# Disch_Sch.net
KiCad netlist of a schematic drawn in Altium Designer
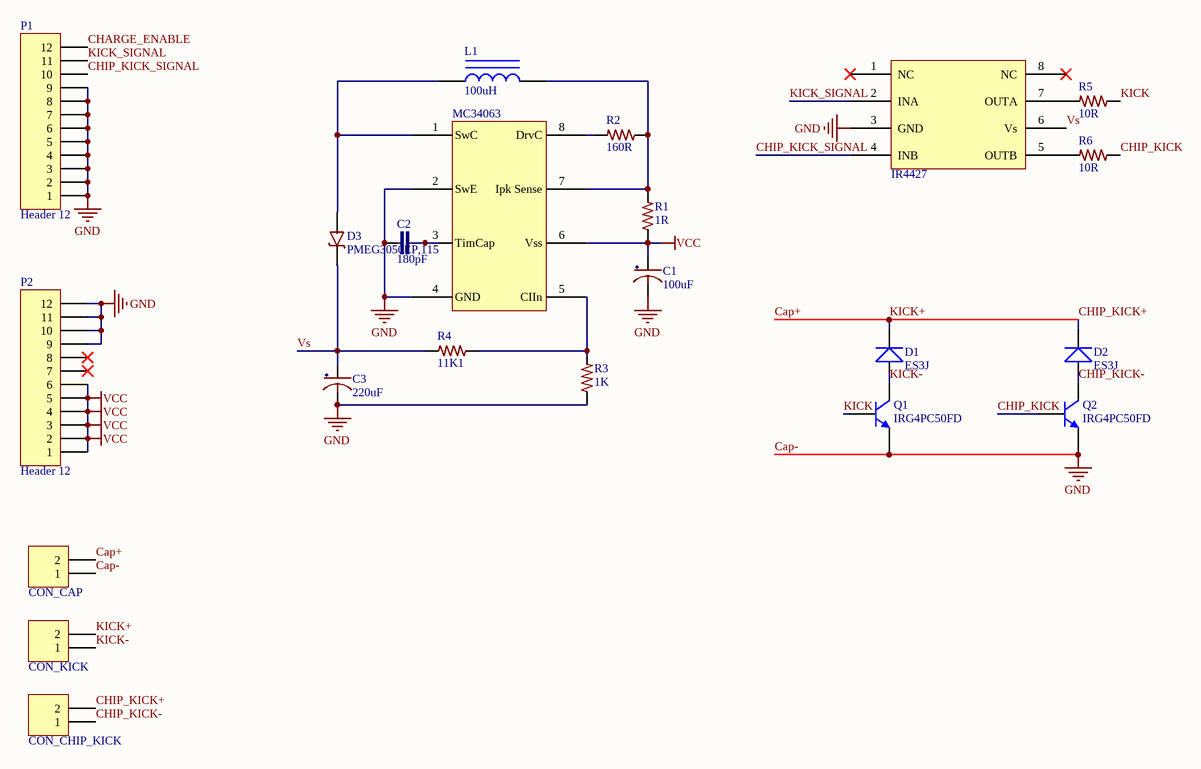
[diagram p0: Disch_Sch.SchDoc]

(export (version "E")
  (design (tool "Eeschema 10.0.6"))
  (components
    (comp (ref "C1")
      (value "100uF")
      (footprint "7343-CAPPOL")
      (description "CAP TANT 100uF 25V 20% ESR = 30mOhm @ 100 kHz")
      (fields (field (name "PART NO") "T521X107M025ATE030"))
      (libsource (lib "IMBEL") (part "CT2917-100uF-1"))
    )
    (comp (ref "C2")
      (value "180pF")
      (footprint "0805-CAP")
      (description "CAP CER 180PF 50V NP0 0805")
      (fields (field (name "PART NO") "C0805C181K5GACTU"))
      (libsource (lib "IMBEL") (part "CC0805-180pF-2"))
    )
    (comp (ref "C3")
      (value "220uF")
      (footprint "NIC-CAPA2-10X10_V")
      (description "CAP ALUM 220uF 20% 50V  ESR = 0,18 ohms  Radial DIA 10mm HEIGH 10,2mm")
      (fields (field (name "PART NO") "EEEFK1H221P"))
      (libsource (lib "IMBEL") (part "CAPACITOR-POL"))
    )
    (comp (ref "CON_CAP")
      (value "OSTTA024163")
      (footprint "Term Block 2P")
      (description "2 Position Wire to Board Terminal Block Horizontal with Board 0.200\" (5.08mm) Through Hole")
      (libsource (lib "Schlib1") (part "Term Block 2P"))
    )
    (comp (ref "CON_CHIP_KICK")
      (value "OSTTA024163")
      (footprint "Term Block 2P")
      (description "2 Position Wire to Board Terminal Block Horizontal with Board 0.200\" (5.08mm) Through Hole")
      (libsource (lib "Schlib1") (part "Term Block 2P"))
    )
    (comp (ref "CON_KICK")
      (value "OSTTA024163")
      (footprint "Term Block 2P")
      (description "2 Position Wire to Board Terminal Block Horizontal with Board 0.200\" (5.08mm) Through Hole")
      (libsource (lib "Schlib1") (part "Term Block 2P"))
    )
    (comp (ref "D1") (value "ES3J") (footprint "Diode") (libsource (lib "KickerSchlib") (part "ES3J")))
    (comp (ref "D2") (value "ES3J") (footprint "Diode") (libsource (lib "KickerSchlib") (part "ES3J")))
    (comp (ref "D3")
      (value "PMEG3050EP,115")
      (footprint "PCBComponent")
      (description "DIODE SCHOTTKY 30V 5A SOD128")
      (libsource (lib "IMBEL") (part "PMEG3050EP,115-01.A.5"))
    )
    (comp (ref "IR4427")
      (value "GATE DRIVER")
      (footprint "IR4427")
      (description "IC DRIVER DUAL LOW SIDE 8-SOIC")
      (libsource (lib "KickerSchlib") (part "IR4427"))
    )
    (comp (ref "L1")
      (value "100uH")
      (footprint "INDUCTOR")
      (description "Fixed Inductors 100uH 0.86A SMT")
      (libsource (lib "KickerSchlib") (part "Inductor"))
    )
    (comp (ref "MC34063")
      (value "Switching Voltage Regulator")
      (footprint "MC34063")
      (libsource (lib "Schlib1") (part "MC34063"))
    )
    (comp (ref "P1")
      (value "Header 12")
      (footprint "HDR1X12")
      (description "Header, 12-Pin")
      (fields (field (name "PUBLISHER") "Altium Limited"))
      (libsource (lib "Miscellaneous Connectors") (part "Header 12"))
    )
    (comp (ref "P2")
      (value "Header 12")
      (footprint "HDR1X12")
      (description "Header, 12-Pin")
      (fields (field (name "PUBLISHER") "Altium Limited"))
      (libsource (lib "Miscellaneous Connectors") (part "Header 12"))
    )
    (comp (ref "Q1")
      (value "IRG4PC50FD")
      (footprint "IRG4PC50FD")
      (description "IGBT Transistors 600V FAST 1-8 KHZ COPACK IGBT")
      (fields (field (name "PUBLISHER") "RoboIME"))
      (libsource (lib "KickerSchlib") (part "IRG4PC50FD"))
    )
    (comp (ref "Q2")
      (value "IRG4PC50FD")
      (footprint "IRG4PC50FD")
      (description "IGBT Transistors 600V FAST 1-8 KHZ COPACK IGBT")
      (fields (field (name "PUBLISHER") "RoboIME"))
      (libsource (lib "KickerSchlib") (part "IRG4PC50FD"))
    )
    (comp (ref "R1")
      (value "1R")
      (footprint "0805-RES")
      (description "RES SMD 1 OHM 1% 1/8W 0805")
      (fields (field (name "PART NO") "CRCW08051R00FKEA"))
      (libsource (lib "IMBEL") (part "R0805-1R-1%-1"))
    )
    (comp (ref "R2")
      (value "160R")
      (footprint "0805-RES")
      (description "RES 160 OHM 1/8W .5% 0805 SMD")
      (fields (field (name "PART NO") "ERA-6AED161V"))
      (libsource (lib "IMBEL") (part "R0805-160R-5"))
    )
    (comp (ref "R3")
      (value "1K")
      (footprint "0402-RES-HD")
      (description "RES 1K OHM 1/10W 1% 0402 SMD")
      (fields (field (name "PART NO") "ERJ-2RKF1001X"))
      (libsource (lib "IMBEL") (part "R0402-1K-A.9"))
    )
    (comp (ref "R4")
      (value "11K1")
      (footprint "0402-RES-HD")
      (description "RES 11.1 KOHM 1/16W 0.1% 0402 SMD")
      (fields (field (name "PART NO") "TNPW040211K1BEED"))
      (libsource (lib "IMBEL") (part "R0402-11K1-1"))
    )
    (comp (ref "R5")
      (value "10R")
      (footprint "0402-RES-HD")
      (description "RES 10 OHM 1/10W 1% 0402 SMD")
      (fields (field (name "PART NO") "ERJ-2RKF10R0X"))
      (libsource (lib "IMBEL") (part "RESISTOR"))
    )
    (comp (ref "R6")
      (value "10R")
      (footprint "0402-RES-HD")
      (description "RES 10 OHM 1/10W 1% 0402 SMD")
      (fields (field (name "PART NO") "ERJ-2RKF10R0X"))
      (libsource (lib "IMBEL") (part "RESISTOR"))
    )
  )
  (nets
    (net (code "1") (name "/CHARGE_ENABLE") (class "Default")
      (node (ref "P1") (pin "12") (pinfunction "12_12") (pintype "passive"))
    )
    (net (code "2") (name "/CHIP_KICK") (class "Default")
      (node (ref "Q2") (pin "2") (pinfunction "G_2") (pintype "passive"))
      (node (ref "R6") (pin "2") (pinfunction "2_2") (pintype "passive"))
    )
    (net (code "3") (name "/CHIP_KICK+") (class "Default")
      (node (ref "CON_CAP") (pin "2") (pinfunction "2_2") (pintype "passive"))
      (node (ref "CON_CHIP_KICK") (pin "2") (pinfunction "2_2") (pintype "passive"))
      (node (ref "CON_KICK") (pin "2") (pinfunction "2_2") (pintype "passive"))
      (node (ref "D1") (pin "D1+") (pinfunction "D1+_D1+") (pintype "passive"))
      (node (ref "D2") (pin "D1+") (pinfunction "D1+_D1+") (pintype "passive"))
    )
    (net (code "4") (name "/CHIP_KICK-") (class "Default")
      (node (ref "CON_CHIP_KICK") (pin "1") (pinfunction "1_1") (pintype "passive"))
      (node (ref "D2") (pin "D1-") (pinfunction "D1-_D1-") (pintype "passive"))
      (node (ref "Q2") (pin "1") (pinfunction "C_1") (pintype "passive"))
    )
    (net (code "5") (name "/CHIP_KICK_SIGNAL") (class "Default")
      (node (ref "IR4427") (pin "4") (pinfunction "INB_4") (pintype "passive"))
      (node (ref "P1") (pin "10") (pinfunction "10_10") (pintype "passive"))
    )
    (net (code "6") (name "/KICK") (class "Default")
      (node (ref "Q1") (pin "2") (pinfunction "G_2") (pintype "passive"))
      (node (ref "R5") (pin "2") (pinfunction "2_2") (pintype "passive"))
    )
    (net (code "7") (name "/KICK-") (class "Default")
      (node (ref "CON_KICK") (pin "1") (pinfunction "1_1") (pintype "passive"))
      (node (ref "D1") (pin "D1-") (pinfunction "D1-_D1-") (pintype "passive"))
      (node (ref "Q1") (pin "1") (pinfunction "C_1") (pintype "passive"))
    )
    (net (code "8") (name "/KICK_SIGNAL") (class "Default")
      (node (ref "IR4427") (pin "2") (pinfunction "INA_2") (pintype "passive"))
      (node (ref "P1") (pin "11") (pinfunction "11_11") (pintype "passive"))
    )
    (net (code "9") (name "/Vs") (class "Default")
      (node (ref "C3") (pin "1") (pinfunction "+_1") (pintype "passive"))
      (node (ref "D3") (pin "1") (pinfunction "C_1") (pintype "passive"))
      (node (ref "IR4427") (pin "6") (pinfunction "Vs_6") (pintype "passive"))
      (node (ref "R4") (pin "1") (pinfunction "1_1") (pintype "passive"))
    )
    (net (code "10") (name "GND") (class "Default")
      (node (ref "C1") (pin "2") (pinfunction "-_2") (pintype "passive"))
      (node (ref "C2") (pin "1") (pinfunction "1_1") (pintype "passive"))
      (node (ref "C3") (pin "2") (pinfunction "-_2") (pintype "passive"))
      (node (ref "CON_CAP") (pin "1") (pinfunction "1_1") (pintype "passive"))
      (node (ref "IR4427") (pin "3") (pinfunction "GND_3") (pintype "passive"))
      (node (ref "MC34063") (pin "2") (pinfunction "SwE_2") (pintype "passive"))
      (node (ref "MC34063") (pin "4") (pinfunction "GND_4") (pintype "passive"))
      (node (ref "P1") (pin "1") (pinfunction "1_1") (pintype "passive"))
      (node (ref "P1") (pin "2") (pinfunction "2_2") (pintype "passive"))
      (node (ref "P1") (pin "3") (pinfunction "3_3") (pintype "passive"))
      (node (ref "P1") (pin "4") (pinfunction "4_4") (pintype "passive"))
      (node (ref "P1") (pin "5") (pinfunction "5_5") (pintype "passive"))
      (node (ref "P1") (pin "6") (pinfunction "6_6") (pintype "passive"))
      (node (ref "P1") (pin "7") (pinfunction "7_7") (pintype "passive"))
      (node (ref "P1") (pin "8") (pinfunction "8_8") (pintype "passive"))
      (node (ref "P1") (pin "9") (pinfunction "9_9") (pintype "passive"))
      (node (ref "P2") (pin "10") (pinfunction "10_10") (pintype "passive"))
      (node (ref "P2") (pin "11") (pinfunction "11_11") (pintype "passive"))
      (node (ref "P2") (pin "12") (pinfunction "12_12") (pintype "passive"))
      (node (ref "P2") (pin "9") (pinfunction "9_9") (pintype "passive"))
      (node (ref "Q1") (pin "3") (pinfunction "E_3") (pintype "passive"))
      (node (ref "Q2") (pin "3") (pinfunction "E_3") (pintype "passive"))
      (node (ref "R3") (pin "1") (pinfunction "1_1") (pintype "passive"))
    )
    (net (code "11") (name "Net-(D3-A)") (class "Default")
      (node (ref "D3") (pin "2") (pinfunction "A_2") (pintype "passive"))
      (node (ref "L1") (pin "1") (pinfunction "1_1") (pintype "passive"))
      (node (ref "MC34063") (pin "1") (pinfunction "SwC_1") (pintype "passive"))
    )
    (net (code "12") (name "Net-(IR4427-OUTA)") (class "Default")
      (node (ref "IR4427") (pin "7") (pinfunction "OUTA_7") (pintype "passive"))
      (node (ref "R5") (pin "1") (pinfunction "1_1") (pintype "passive"))
    )
    (net (code "13") (name "Net-(IR4427-OUTB)") (class "Default")
      (node (ref "IR4427") (pin "5") (pinfunction "OUTB_5") (pintype "passive"))
      (node (ref "R6") (pin "1") (pinfunction "1_1") (pintype "passive"))
    )
    (net (code "14") (name "Net-(MC34063-CIIn)") (class "Default")
      (node (ref "MC34063") (pin "5") (pinfunction "CIIn_5") (pintype "passive"))
      (node (ref "R3") (pin "2") (pinfunction "2_2") (pintype "passive"))
      (node (ref "R4") (pin "2") (pinfunction "2_2") (pintype "passive"))
    )
    (net (code "15") (name "Net-(MC34063-DrvC)") (class "Default")
      (node (ref "MC34063") (pin "8") (pinfunction "DrvC_8") (pintype "passive"))
      (node (ref "R2") (pin "1") (pinfunction "1_1") (pintype "passive"))
    )
    (net (code "16") (name "Net-(MC34063-Ipk_Sense)") (class "Default")
      (node (ref "L1") (pin "2") (pinfunction "2_2") (pintype "passive"))
      (node (ref "MC34063") (pin "7") (pinfunction "Ipk_Sense_7") (pintype "passive"))
      (node (ref "R1") (pin "2") (pinfunction "2_2") (pintype "passive"))
      (node (ref "R2") (pin "2") (pinfunction "2_2") (pintype "passive"))
    )
    (net (code "17") (name "Net-(MC34063-TimCap)") (class "Default")
      (node (ref "C2") (pin "2") (pinfunction "2_2") (pintype "passive"))
      (node (ref "MC34063") (pin "3") (pinfunction "TimCap_3") (pintype "passive"))
    )
    (net (code "18") (name "VCC") (class "Default")
      (node (ref "C1") (pin "1") (pinfunction "+_1") (pintype "passive"))
      (node (ref "MC34063") (pin "6") (pinfunction "Vss_6") (pintype "passive"))
      (node (ref "P2") (pin "1") (pinfunction "1_1") (pintype "passive"))
      (node (ref "P2") (pin "2") (pinfunction "2_2") (pintype "passive"))
      (node (ref "P2") (pin "3") (pinfunction "3_3") (pintype "passive"))
      (node (ref "P2") (pin "4") (pinfunction "4_4") (pintype "passive"))
      (node (ref "P2") (pin "5") (pinfunction "5_5") (pintype "passive"))
      (node (ref "P2") (pin "6") (pinfunction "6_6") (pintype "passive"))
      (node (ref "R1") (pin "1") (pinfunction "1_1") (pintype "passive"))
    )
    (net (code "19") (name "unconnected-(IR4427-NC-Pad1)") (class "Default")
      (node (ref "IR4427") (pin "1") (pinfunction "NC_1") (pintype "passive+no_connect"))
    )
    (net (code "20") (name "unconnected-(IR4427-NC-Pad8)") (class "Default")
      (node (ref "IR4427") (pin "8") (pinfunction "NC_8") (pintype "passive+no_connect"))
    )
    (net (code "21") (name "unconnected-(P2-Pad7)") (class "Default")
      (node (ref "P2") (pin "7") (pinfunction "7_7") (pintype "passive+no_connect"))
    )
    (net (code "22") (name "unconnected-(P2-Pad8)") (class "Default")
      (node (ref "P2") (pin "8") (pinfunction "8_8") (pintype "passive+no_connect"))
    )
  )
)
